# speedometer.net
KiCad netlist of a schematic drawn in EAGLE
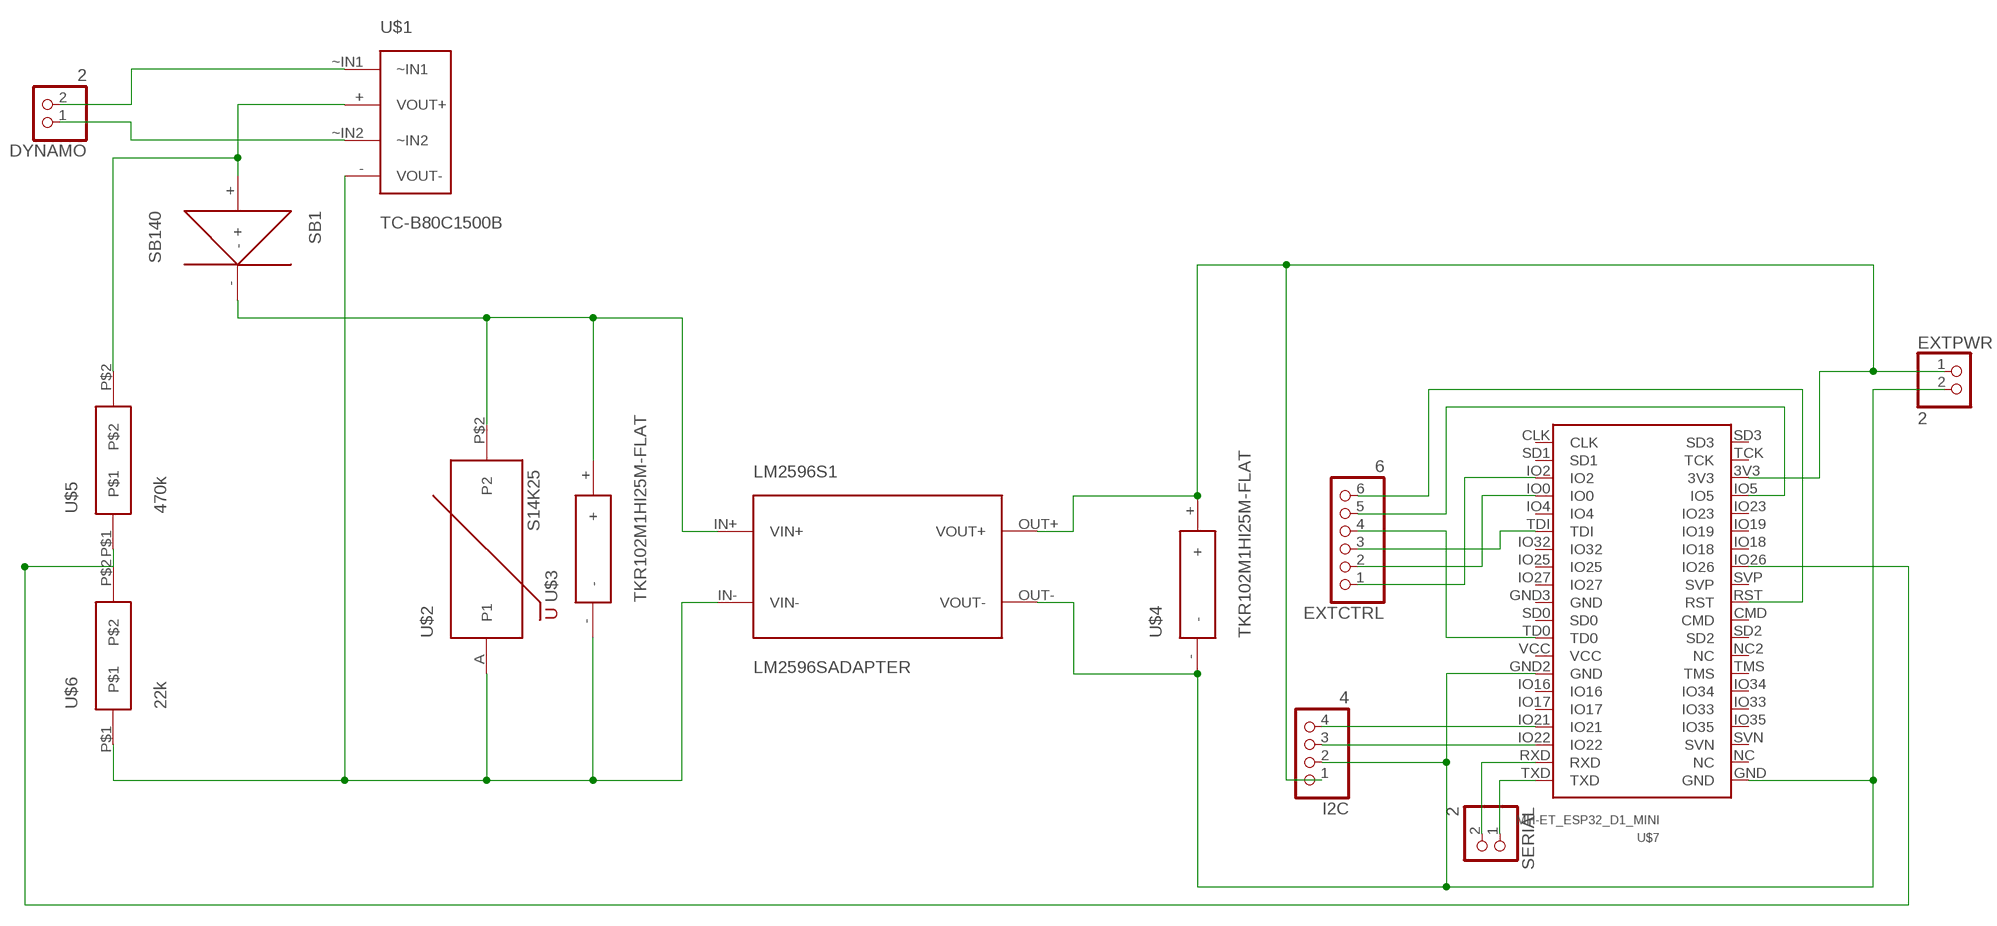
[diagram p0: schematic, sheet 1]

(export (version "E")
  (design (tool "Eeschema 10.0.6"))
  (components
    (comp (ref "DYNAMO")
      (value "2")
      (footprint "eagle-import:1X02")
      (libsource (lib "eagle-import") (part "PINHD-1X2"))
    )
    (comp (ref "EXTCTRL")
      (value "6")
      (footprint "eagle-import:1X06")
      (libsource (lib "eagle-import") (part "PINHD-1X6"))
    )
    (comp (ref "EXTPWR")
      (value "2")
      (footprint "eagle-import:1X02")
      (libsource (lib "eagle-import") (part "PINHD-1X2"))
    )
    (comp (ref "I2C")
      (value "4")
      (footprint "eagle-import:1X04")
      (libsource (lib "eagle-import") (part "PINHD-1X4"))
    )
    (comp (ref "LM2596S1")
      (value "LM2596SADAPTER")
      (footprint "eagle-import:LM2596SADAPTER")
      (libsource (lib "eagle-import") (part "LM2596SADAPTER"))
    )
    (comp (ref "SB1")
      (value "SB140")
      (footprint "eagle-import:SB140")
      (libsource (lib "eagle-import") (part "SB140"))
    )
    (comp (ref "SERIAL")
      (value "2")
      (footprint "eagle-import:1X02")
      (libsource (lib "eagle-import") (part "PINHD-1X2"))
    )
    (comp (ref "U$1")
      (value "TC-B80C1500B")
      (footprint "eagle-import:TC-B80C1500B")
      (libsource (lib "eagle-import") (part "TC-B80C1500B"))
    )
    (comp (ref "U$2")
      (value "S14K25")
      (footprint "eagle-import:S14K25")
      (libsource (lib "eagle-import") (part "S14K25"))
    )
    (comp (ref "U$3")
      (value "TKR102M1HI25M-FLAT")
      (footprint "eagle-import:TKR102M1HI25M-FLAT")
      (libsource (lib "eagle-import") (part "TKR102M1HI25M-FLAT"))
    )
    (comp (ref "U$4")
      (value "TKR102M1HI25M-FLAT")
      (footprint "eagle-import:TKR102M1HI25M-FLAT")
      (libsource (lib "eagle-import") (part "TKR102M1HI25M-FLAT"))
    )
    (comp (ref "U$5")
      (value "470k")
      (footprint "eagle-import:RESISTOR")
      (libsource (lib "eagle-import") (part "RESISTOR"))
    )
    (comp (ref "U$6")
      (value "22k")
      (footprint "eagle-import:RESISTOR")
      (libsource (lib "eagle-import") (part "RESISTOR"))
    )
    (comp (ref "U$7")
      (value "MH-ET_ESP32_D1_MINI")
      (footprint "eagle-import:MH-ET_ESP32_D1_MINI")
      (libsource (lib "eagle-import") (part "MH-ET_ESP32_D1_MINI"))
    )
  )
  (nets
    (net (code "1") (name "Net-(EXTCTRL-Pad1)") (class "Default")
      (node (ref "EXTCTRL") (pin "1") (pinfunction "1_1") (pintype "passive"))
      (node (ref "U$7") (pin "IO2") (pinfunction "IO2_IO2") (pintype "bidirectional"))
    )
    (net (code "2") (name "Net-(EXTCTRL-Pad2)") (class "Default")
      (node (ref "EXTCTRL") (pin "2") (pinfunction "2_2") (pintype "passive"))
      (node (ref "U$7") (pin "IO0") (pinfunction "IO0_IO0") (pintype "bidirectional"))
    )
    (net (code "3") (name "Net-(EXTCTRL-Pad3)") (class "Default")
      (node (ref "EXTCTRL") (pin "3") (pinfunction "3_3") (pintype "passive"))
      (node (ref "U$7") (pin "TDI") (pinfunction "TDI_TDI") (pintype "bidirectional"))
    )
    (net (code "4") (name "Net-(EXTCTRL-Pad4)") (class "Default")
      (node (ref "EXTCTRL") (pin "4") (pinfunction "4_4") (pintype "passive"))
      (node (ref "U$7") (pin "TD0") (pinfunction "TD0_TD0") (pintype "bidirectional"))
    )
    (net (code "5") (name "Net-(EXTCTRL-Pad5)") (class "Default")
      (node (ref "EXTCTRL") (pin "5") (pinfunction "5_5") (pintype "passive"))
      (node (ref "U$7") (pin "IO5") (pinfunction "IO5_IO5") (pintype "bidirectional"))
    )
    (net (code "6") (name "Net-(EXTCTRL-Pad6)") (class "Default")
      (node (ref "EXTCTRL") (pin "6") (pinfunction "6_6") (pintype "passive"))
      (node (ref "U$7") (pin "RST") (pinfunction "RST_RST") (pintype "bidirectional"))
    )
    (net (code "7") (name "Net-(I2C-Pad3)") (class "Default")
      (node (ref "I2C") (pin "3") (pinfunction "3_3") (pintype "passive"))
      (node (ref "U$7") (pin "IO22") (pinfunction "IO22_IO22") (pintype "bidirectional"))
    )
    (net (code "8") (name "Net-(I2C-Pad4)") (class "Default")
      (node (ref "I2C") (pin "4") (pinfunction "4_4") (pintype "passive"))
      (node (ref "U$7") (pin "IO21") (pinfunction "IO21_IO21") (pintype "bidirectional"))
    )
    (net (code "9") (name "Net-(LM2596S1-VIN+)") (class "Default")
      (node (ref "LM2596S1") (pin "IN+") (pinfunction "VIN+_IN+") (pintype "bidirectional"))
      (node (ref "SB1") (pin "-") (pinfunction "-_-") (pintype "bidirectional"))
      (node (ref "U$2") (pin "P$2") (pinfunction "P2_P$2") (pintype "bidirectional"))
      (node (ref "U$3") (pin "+") (pinfunction "+_+") (pintype "bidirectional"))
    )
    (net (code "10") (name "Net-(LM2596S1-VIN-)") (class "Default")
      (node (ref "LM2596S1") (pin "IN-") (pinfunction "VIN-_IN-") (pintype "bidirectional"))
      (node (ref "U$1") (pin "-") (pinfunction "VOUT-_-") (pintype "bidirectional"))
      (node (ref "U$2") (pin "A") (pinfunction "P1_A") (pintype "bidirectional"))
      (node (ref "U$3") (pin "-") (pinfunction "-_-") (pintype "bidirectional"))
      (node (ref "U$6") (pin "P$1") (pinfunction "P$1_P$1") (pintype "bidirectional"))
    )
    (net (code "11") (name "Net-(LM2596S1-VOUT+)") (class "Default")
      (node (ref "EXTPWR") (pin "1") (pinfunction "1_1") (pintype "passive"))
      (node (ref "I2C") (pin "1") (pinfunction "1_1") (pintype "passive"))
      (node (ref "LM2596S1") (pin "OUT+") (pinfunction "VOUT+_OUT+") (pintype "bidirectional"))
      (node (ref "U$4") (pin "+") (pinfunction "+_+") (pintype "bidirectional"))
      (node (ref "U$7") (pin "3V3") (pinfunction "3V3_3V3") (pintype "bidirectional"))
    )
    (net (code "12") (name "Net-(LM2596S1-VOUT-)") (class "Default")
      (node (ref "EXTPWR") (pin "2") (pinfunction "2_2") (pintype "passive"))
      (node (ref "I2C") (pin "2") (pinfunction "2_2") (pintype "passive"))
      (node (ref "LM2596S1") (pin "OUT-") (pinfunction "VOUT-_OUT-") (pintype "bidirectional"))
      (node (ref "U$4") (pin "-") (pinfunction "-_-") (pintype "bidirectional"))
      (node (ref "U$7") (pin "GND") (pinfunction "GND_GND") (pintype "bidirectional"))
      (node (ref "U$7") (pin "GND2") (pinfunction "GND_GND2") (pintype "bidirectional"))
    )
    (net (code "13") (name "Net-(SERIAL-Pad1)") (class "Default")
      (node (ref "SERIAL") (pin "1") (pinfunction "1_1") (pintype "passive"))
      (node (ref "U$7") (pin "TXD") (pinfunction "TXD_TXD") (pintype "bidirectional"))
    )
    (net (code "14") (name "Net-(SERIAL-Pad2)") (class "Default")
      (node (ref "SERIAL") (pin "2") (pinfunction "2_2") (pintype "passive"))
      (node (ref "U$7") (pin "RXD") (pinfunction "RXD_RXD") (pintype "bidirectional"))
    )
    (net (code "15") (name "Net-(U$1-VOUT+)") (class "Default")
      (node (ref "SB1") (pin "+") (pinfunction "+_+") (pintype "bidirectional"))
      (node (ref "U$1") (pin "+") (pinfunction "VOUT+_+") (pintype "bidirectional"))
      (node (ref "U$5") (pin "P$2") (pinfunction "P$2_P$2") (pintype "bidirectional"))
    )
    (net (code "16") (name "Net-(U$1-~{IN1})") (class "Default")
      (node (ref "DYNAMO") (pin "2") (pinfunction "2_2") (pintype "passive"))
      (node (ref "U$1") (pin "~IN1") (pinfunction "~{IN1}_~IN1") (pintype "bidirectional"))
    )
    (net (code "17") (name "Net-(U$1-~{IN2})") (class "Default")
      (node (ref "DYNAMO") (pin "1") (pinfunction "1_1") (pintype "passive"))
      (node (ref "U$1") (pin "~IN2") (pinfunction "~{IN2}_~IN2") (pintype "bidirectional"))
    )
    (net (code "18") (name "Net-(U$5-PadP$1)") (class "Default")
      (node (ref "U$5") (pin "P$1") (pinfunction "P$1_P$1") (pintype "bidirectional"))
      (node (ref "U$6") (pin "P$2") (pinfunction "P$2_P$2") (pintype "bidirectional"))
      (node (ref "U$7") (pin "IO26") (pinfunction "IO26_IO26") (pintype "bidirectional"))
    )
    (net (code "19") (name "unconnected-(U$7-GND-PadGND3)") (class "Default")
      (node (ref "U$7") (pin "GND3") (pinfunction "GND_GND3") (pintype "bidirectional"))
    )
    (net (code "20") (name "unconnected-(U$7-NC-PadNC2)") (class "Default")
      (node (ref "U$7") (pin "NC2") (pinfunction "NC_NC2") (pintype "bidirectional"))
    )
    (net (code "21") (name "unconnected-(U$7-PadCLK)") (class "Default")
      (node (ref "U$7") (pin "CLK") (pinfunction "CLK_CLK") (pintype "bidirectional"))
    )
    (net (code "22") (name "unconnected-(U$7-PadCMD)") (class "Default")
      (node (ref "U$7") (pin "CMD") (pinfunction "CMD_CMD") (pintype "bidirectional"))
    )
    (net (code "23") (name "unconnected-(U$7-PadIO4)") (class "Default")
      (node (ref "U$7") (pin "IO4") (pinfunction "IO4_IO4") (pintype "bidirectional"))
    )
    (net (code "24") (name "unconnected-(U$7-PadIO16)") (class "Default")
      (node (ref "U$7") (pin "IO16") (pinfunction "IO16_IO16") (pintype "bidirectional"))
    )
    (net (code "25") (name "unconnected-(U$7-PadIO17)") (class "Default")
      (node (ref "U$7") (pin "IO17") (pinfunction "IO17_IO17") (pintype "bidirectional"))
    )
    (net (code "26") (name "unconnected-(U$7-PadIO18)") (class "Default")
      (node (ref "U$7") (pin "IO18") (pinfunction "IO18_IO18") (pintype "bidirectional"))
    )
    (net (code "27") (name "unconnected-(U$7-PadIO19)") (class "Default")
      (node (ref "U$7") (pin "IO19") (pinfunction "IO19_IO19") (pintype "bidirectional"))
    )
    (net (code "28") (name "unconnected-(U$7-PadIO23)") (class "Default")
      (node (ref "U$7") (pin "IO23") (pinfunction "IO23_IO23") (pintype "bidirectional"))
    )
    (net (code "29") (name "unconnected-(U$7-PadIO25)") (class "Default")
      (node (ref "U$7") (pin "IO25") (pinfunction "IO25_IO25") (pintype "bidirectional"))
    )
    (net (code "30") (name "unconnected-(U$7-PadIO27)") (class "Default")
      (node (ref "U$7") (pin "IO27") (pinfunction "IO27_IO27") (pintype "bidirectional"))
    )
    (net (code "31") (name "unconnected-(U$7-PadIO32)") (class "Default")
      (node (ref "U$7") (pin "IO32") (pinfunction "IO32_IO32") (pintype "bidirectional"))
    )
    (net (code "32") (name "unconnected-(U$7-PadIO33)") (class "Default")
      (node (ref "U$7") (pin "IO33") (pinfunction "IO33_IO33") (pintype "bidirectional"))
    )
    (net (code "33") (name "unconnected-(U$7-PadIO34)") (class "Default")
      (node (ref "U$7") (pin "IO34") (pinfunction "IO34_IO34") (pintype "bidirectional"))
    )
    (net (code "34") (name "unconnected-(U$7-PadIO35)") (class "Default")
      (node (ref "U$7") (pin "IO35") (pinfunction "IO35_IO35") (pintype "bidirectional"))
    )
    (net (code "35") (name "unconnected-(U$7-PadNC)") (class "Default")
      (node (ref "U$7") (pin "NC") (pinfunction "NC_NC") (pintype "bidirectional"))
    )
    (net (code "36") (name "unconnected-(U$7-PadSD0)") (class "Default")
      (node (ref "U$7") (pin "SD0") (pinfunction "SD0_SD0") (pintype "bidirectional"))
    )
    (net (code "37") (name "unconnected-(U$7-PadSD1)") (class "Default")
      (node (ref "U$7") (pin "SD1") (pinfunction "SD1_SD1") (pintype "bidirectional"))
    )
    (net (code "38") (name "unconnected-(U$7-PadSD2)") (class "Default")
      (node (ref "U$7") (pin "SD2") (pinfunction "SD2_SD2") (pintype "bidirectional"))
    )
    (net (code "39") (name "unconnected-(U$7-PadSD3)") (class "Default")
      (node (ref "U$7") (pin "SD3") (pinfunction "SD3_SD3") (pintype "bidirectional"))
    )
    (net (code "40") (name "unconnected-(U$7-PadSVN)") (class "Default")
      (node (ref "U$7") (pin "SVN") (pinfunction "SVN_SVN") (pintype "bidirectional"))
    )
    (net (code "41") (name "unconnected-(U$7-PadSVP)") (class "Default")
      (node (ref "U$7") (pin "SVP") (pinfunction "SVP_SVP") (pintype "bidirectional"))
    )
    (net (code "42") (name "unconnected-(U$7-PadTCK)") (class "Default")
      (node (ref "U$7") (pin "TCK") (pinfunction "TCK_TCK") (pintype "bidirectional"))
    )
    (net (code "43") (name "unconnected-(U$7-PadTMS)") (class "Default")
      (node (ref "U$7") (pin "TMS") (pinfunction "TMS_TMS") (pintype "bidirectional"))
    )
    (net (code "44") (name "unconnected-(U$7-PadVCC)") (class "Default")
      (node (ref "U$7") (pin "VCC") (pinfunction "VCC_VCC") (pintype "bidirectional"))
    )
  )
)
